# Sheet1.net
KiCad netlist of a schematic drawn in Altium Designer
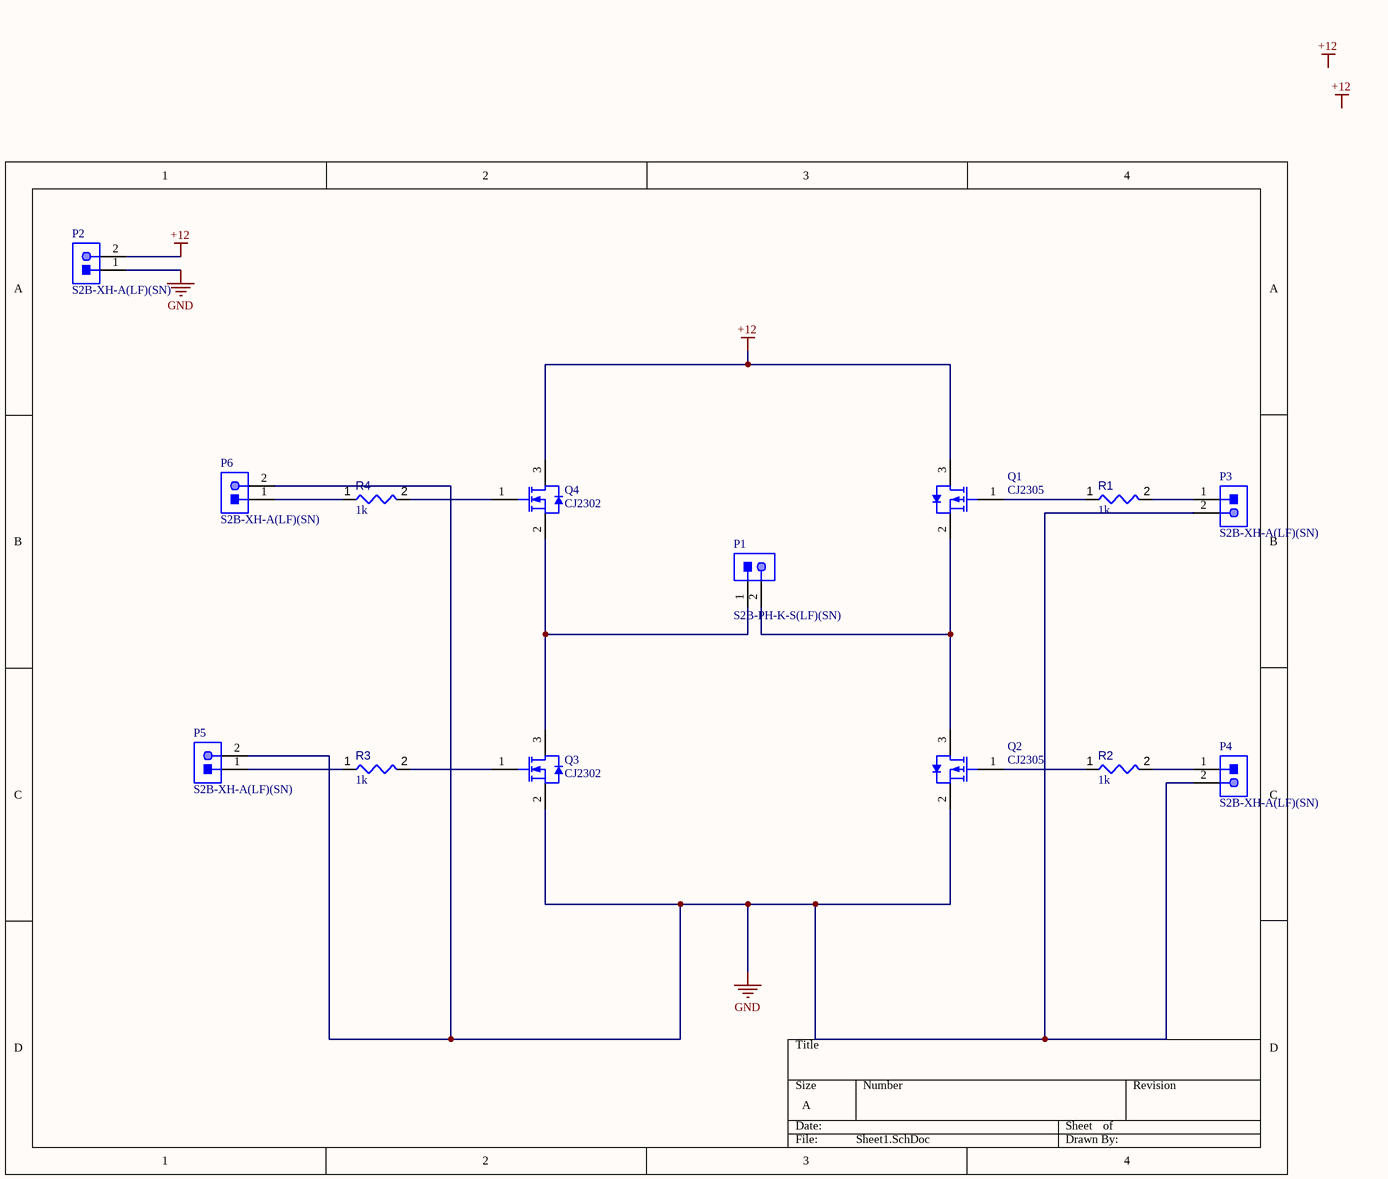
[diagram p0: Sheet1.SchDoc]

(export (version "E")
  (design (tool "Eeschema 10.0.6"))
  (components
    (comp (ref "P1")
      (value "S2B-PH-K-S(LF)(SN)")
      (footprint "JST-S2B-PH-K-S_V")
      (fields (field (name "MANUFACTURER") "Japan Solderless Terminals"))
      (libsource (lib "") (part "CN-1P-M-R2_2"))
    )
    (comp (ref "P2")
      (value "S2B-XH-A(LF)(SN)")
      (footprint "JST-S2B-XH-A(LF)(SN)_V")
      (fields (field (name "MANUFACTURER") "JST"))
      (libsource (lib "wne-theremin") (part "CN-1P-M-R2"))
    )
    (comp (ref "P3")
      (value "S2B-XH-A(LF)(SN)")
      (footprint "JST-S2B-XH-A(LF)(SN)_V")
      (fields (field (name "MANUFACTURER") "JST"))
      (libsource (lib "") (part "CN-1P-M-R2_1"))
    )
    (comp (ref "P4")
      (value "S2B-XH-A(LF)(SN)")
      (footprint "JST-S2B-XH-A(LF)(SN)_V")
      (fields (field (name "MANUFACTURER") "JST"))
      (libsource (lib "") (part "CN-1P-M-R2_1"))
    )
    (comp (ref "P5")
      (value "S2B-XH-A(LF)(SN)")
      (footprint "JST-S2B-XH-A(LF)(SN)_V")
      (fields (field (name "MANUFACTURER") "JST"))
      (libsource (lib "wne-theremin") (part "CN-1P-M-R2"))
    )
    (comp (ref "P6")
      (value "S2B-XH-A(LF)(SN)")
      (footprint "JST-S2B-XH-A(LF)(SN)_V")
      (fields (field (name "MANUFACTURER") "JST"))
      (libsource (lib "wne-theremin") (part "CN-1P-M-R2"))
    )
    (comp (ref "Q1")
      (value "CJ2305")
      (footprint "JSCJ-SOT23-3_V")
      (description "P-Channel Plastic Encapsulate MOSFET, 12 V, 4.1 A, 3-Pin SOT23, Tape and Reel")
      (fields (field (name "MANUFACTURER") "Jiangsu Changjiang Electronics Technology"))
      (libsource (lib "wne-theremin") (part "PEMOS-GSD-3"))
    )
    (comp (ref "Q2")
      (value "CJ2305")
      (footprint "JSCJ-SOT23-3_V")
      (description "P-Channel Plastic Encapsulate MOSFET, 12 V, 4.1 A, 3-Pin SOT23, Tape and Reel")
      (fields (field (name "MANUFACTURER") "Jiangsu Changjiang Electronics Technology"))
      (libsource (lib "wne-theremin") (part "PEMOS-GSD-3"))
    )
    (comp (ref "Q3")
      (value "CJ2302")
      (footprint "JSCJ-SOT23-3_V")
      (description "N-Channe Plastic Encapsulate MOSFET, 20 V, 2.1 A, 3-Pin SOT23, Tape and Reel")
      (fields (field (name "MANUFACTURER") "Jiangsu Changjiang Electronics Technology"))
      (libsource (lib "wne-theremin") (part "NEMOS-GSD-3"))
    )
    (comp (ref "Q4")
      (value "CJ2302")
      (footprint "JSCJ-SOT23-3_V")
      (description "N-Channe Plastic Encapsulate MOSFET, 20 V, 2.1 A, 3-Pin SOT23, Tape and Reel")
      (fields (field (name "MANUFACTURER") "Jiangsu Changjiang Electronics Technology"))
      (libsource (lib "wne-theremin") (part "NEMOS-GSD-3"))
    )
    (comp (ref "R1")
      (value "1k")
      (footprint "RESA60-630X240")
      (description "Axial Resistor, 10 KOhm, +/- 1%, 0.25 W, -55 to 155 degC, 2-Pin THD, RoHS, Bulk")
      (fields (field (name "TOLERANCE") "1%") (field (name "POWER") "250mW"))
      (libsource (lib "wne-theremin") (part "RES-2"))
    )
    (comp (ref "R2")
      (value "1k")
      (footprint "RESA60-630X240")
      (description "Axial Resistor, 10 KOhm, +/- 1%, 0.25 W, -55 to 155 degC, 2-Pin THD, RoHS, Bulk")
      (fields (field (name "TOLERANCE") "1%") (field (name "POWER") "250mW"))
      (libsource (lib "wne-theremin") (part "RES-2"))
    )
    (comp (ref "R3")
      (value "1k")
      (footprint "RESA60-630X240")
      (description "Axial Resistor, 10 KOhm, +/- 1%, 0.25 W, -55 to 155 degC, 2-Pin THD, RoHS, Bulk")
      (fields (field (name "TOLERANCE") "1%") (field (name "POWER") "250mW"))
      (libsource (lib "wne-theremin") (part "RES-2"))
    )
    (comp (ref "R4")
      (value "1k")
      (footprint "RESA60-630X240")
      (description "Axial Resistor, 10 KOhm, +/- 1%, 0.25 W, -55 to 155 degC, 2-Pin THD, RoHS, Bulk")
      (fields (field (name "TOLERANCE") "1%") (field (name "POWER") "250mW"))
      (libsource (lib "wne-theremin") (part "RES-2"))
    )
  )
  (nets
    (net (code "1") (name "+12") (class "Default")
      (node (ref "P2") (pin "2") (pinfunction "2_2") (pintype "passive"))
      (node (ref "Q1") (pin "3") (pinfunction "DRAIN_3") (pintype "passive"))
      (node (ref "Q4") (pin "3") (pinfunction "D_3") (pintype "passive"))
    )
    (net (code "2") (name "GND") (class "Default")
      (node (ref "P2") (pin "1") (pinfunction "1_1") (pintype "passive"))
      (node (ref "P3") (pin "2") (pinfunction "2_2") (pintype "passive"))
      (node (ref "P4") (pin "2") (pinfunction "2_2") (pintype "passive"))
      (node (ref "P5") (pin "2") (pinfunction "2_2") (pintype "passive"))
      (node (ref "P6") (pin "2") (pinfunction "2_2") (pintype "passive"))
      (node (ref "Q2") (pin "2") (pinfunction "SOURCE_2") (pintype "passive"))
      (node (ref "Q3") (pin "2") (pinfunction "S_2") (pintype "passive"))
    )
    (net (code "3") (name "Net-(P3-Pad1)") (class "Default")
      (node (ref "P3") (pin "1") (pinfunction "1_1") (pintype "passive"))
      (node (ref "R1") (pin "2") (pinfunction "2_2") (pintype "passive"))
    )
    (net (code "4") (name "Net-(P4-Pad1)") (class "Default")
      (node (ref "P4") (pin "1") (pinfunction "1_1") (pintype "passive"))
      (node (ref "R2") (pin "2") (pinfunction "2_2") (pintype "passive"))
    )
    (net (code "5") (name "Net-(P5-Pad1)") (class "Default")
      (node (ref "P5") (pin "1") (pinfunction "1_1") (pintype "passive"))
      (node (ref "R3") (pin "1") (pinfunction "1_1") (pintype "passive"))
    )
    (net (code "6") (name "Net-(P6-Pad1)") (class "Default")
      (node (ref "P6") (pin "1") (pinfunction "1_1") (pintype "passive"))
      (node (ref "R4") (pin "1") (pinfunction "1_1") (pintype "passive"))
    )
    (net (code "7") (name "Net-(Q1-GATE)") (class "Default")
      (node (ref "Q1") (pin "1") (pinfunction "GATE_1") (pintype "passive"))
      (node (ref "R1") (pin "1") (pinfunction "1_1") (pintype "passive"))
    )
    (net (code "8") (name "Net-(Q1-SOURCE)") (class "Default")
      (node (ref "P1") (pin "2") (pinfunction "2_2") (pintype "passive"))
      (node (ref "Q1") (pin "2") (pinfunction "SOURCE_2") (pintype "passive"))
      (node (ref "Q2") (pin "3") (pinfunction "DRAIN_3") (pintype "passive"))
    )
    (net (code "9") (name "Net-(Q2-GATE)") (class "Default")
      (node (ref "Q2") (pin "1") (pinfunction "GATE_1") (pintype "passive"))
      (node (ref "R2") (pin "1") (pinfunction "1_1") (pintype "passive"))
    )
    (net (code "10") (name "Net-(Q3-D)") (class "Default")
      (node (ref "P1") (pin "1") (pinfunction "1_1") (pintype "passive"))
      (node (ref "Q3") (pin "3") (pinfunction "D_3") (pintype "passive"))
      (node (ref "Q4") (pin "2") (pinfunction "S_2") (pintype "passive"))
    )
    (net (code "11") (name "Net-(Q3-G)") (class "Default")
      (node (ref "Q3") (pin "1") (pinfunction "G_1") (pintype "passive"))
      (node (ref "R3") (pin "2") (pinfunction "2_2") (pintype "passive"))
    )
    (net (code "12") (name "Net-(Q4-G)") (class "Default")
      (node (ref "Q4") (pin "1") (pinfunction "G_1") (pintype "passive"))
      (node (ref "R4") (pin "2") (pinfunction "2_2") (pintype "passive"))
    )
  )
)
